# u2x.net
KiCad netlist of a schematic drawn in EAGLE
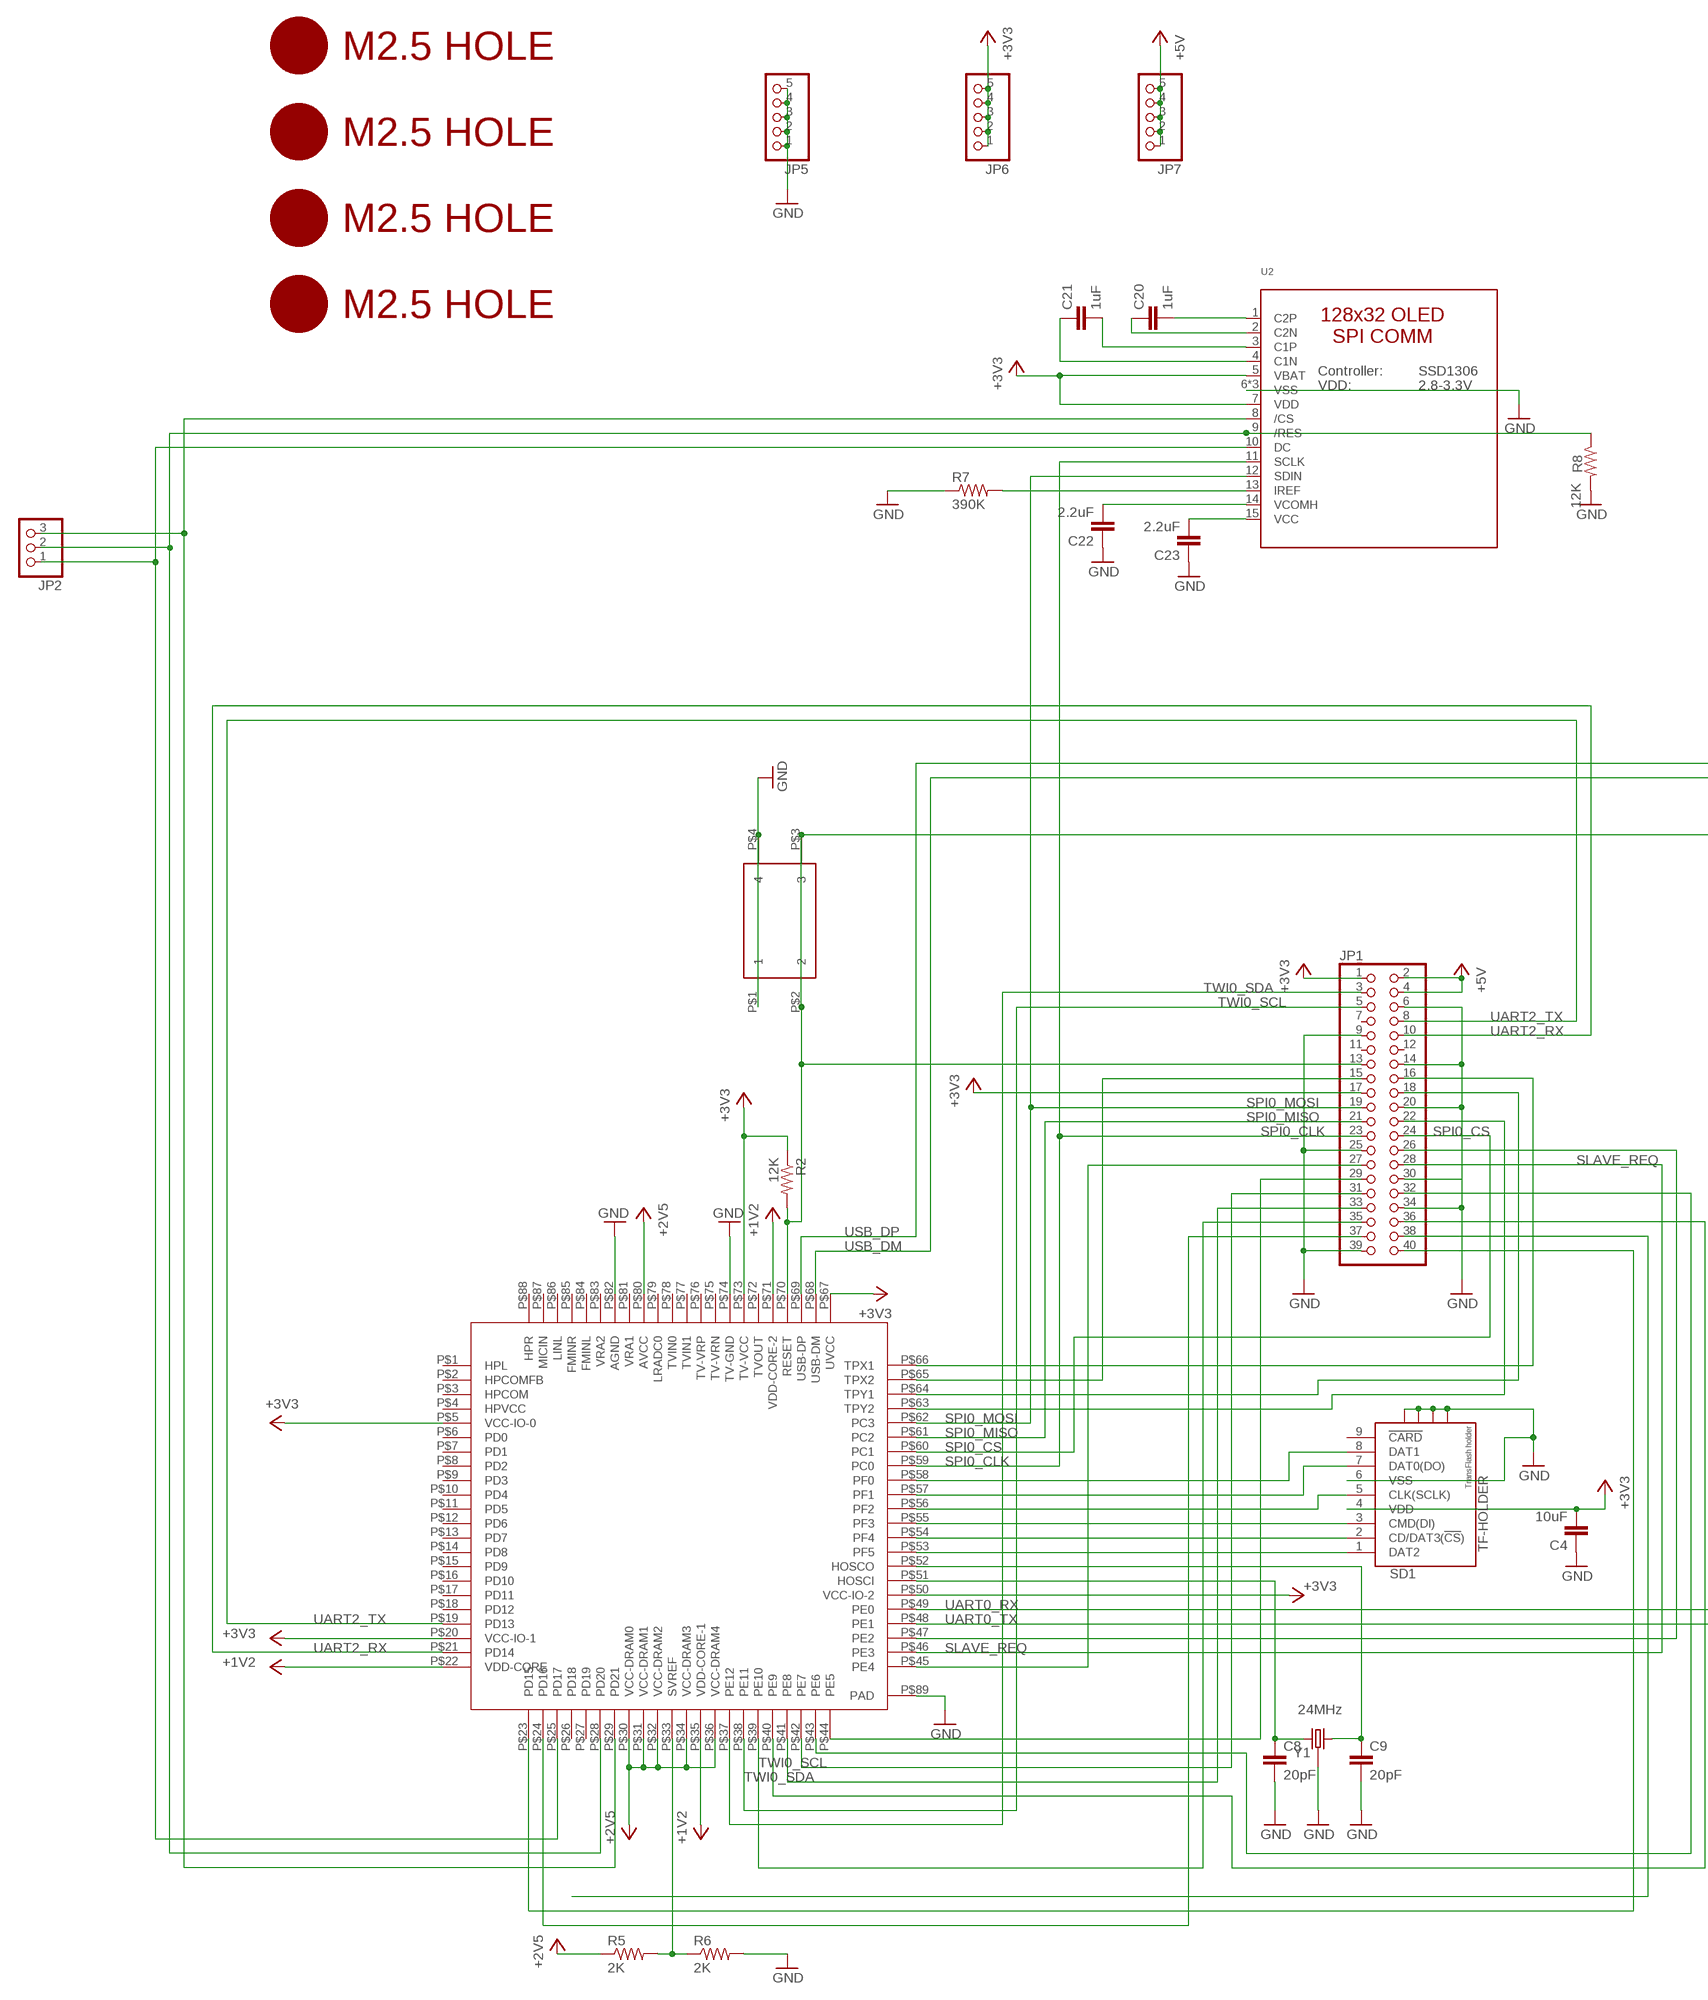
[diagram p0: schematic, sheet 1, part 1 of 2]
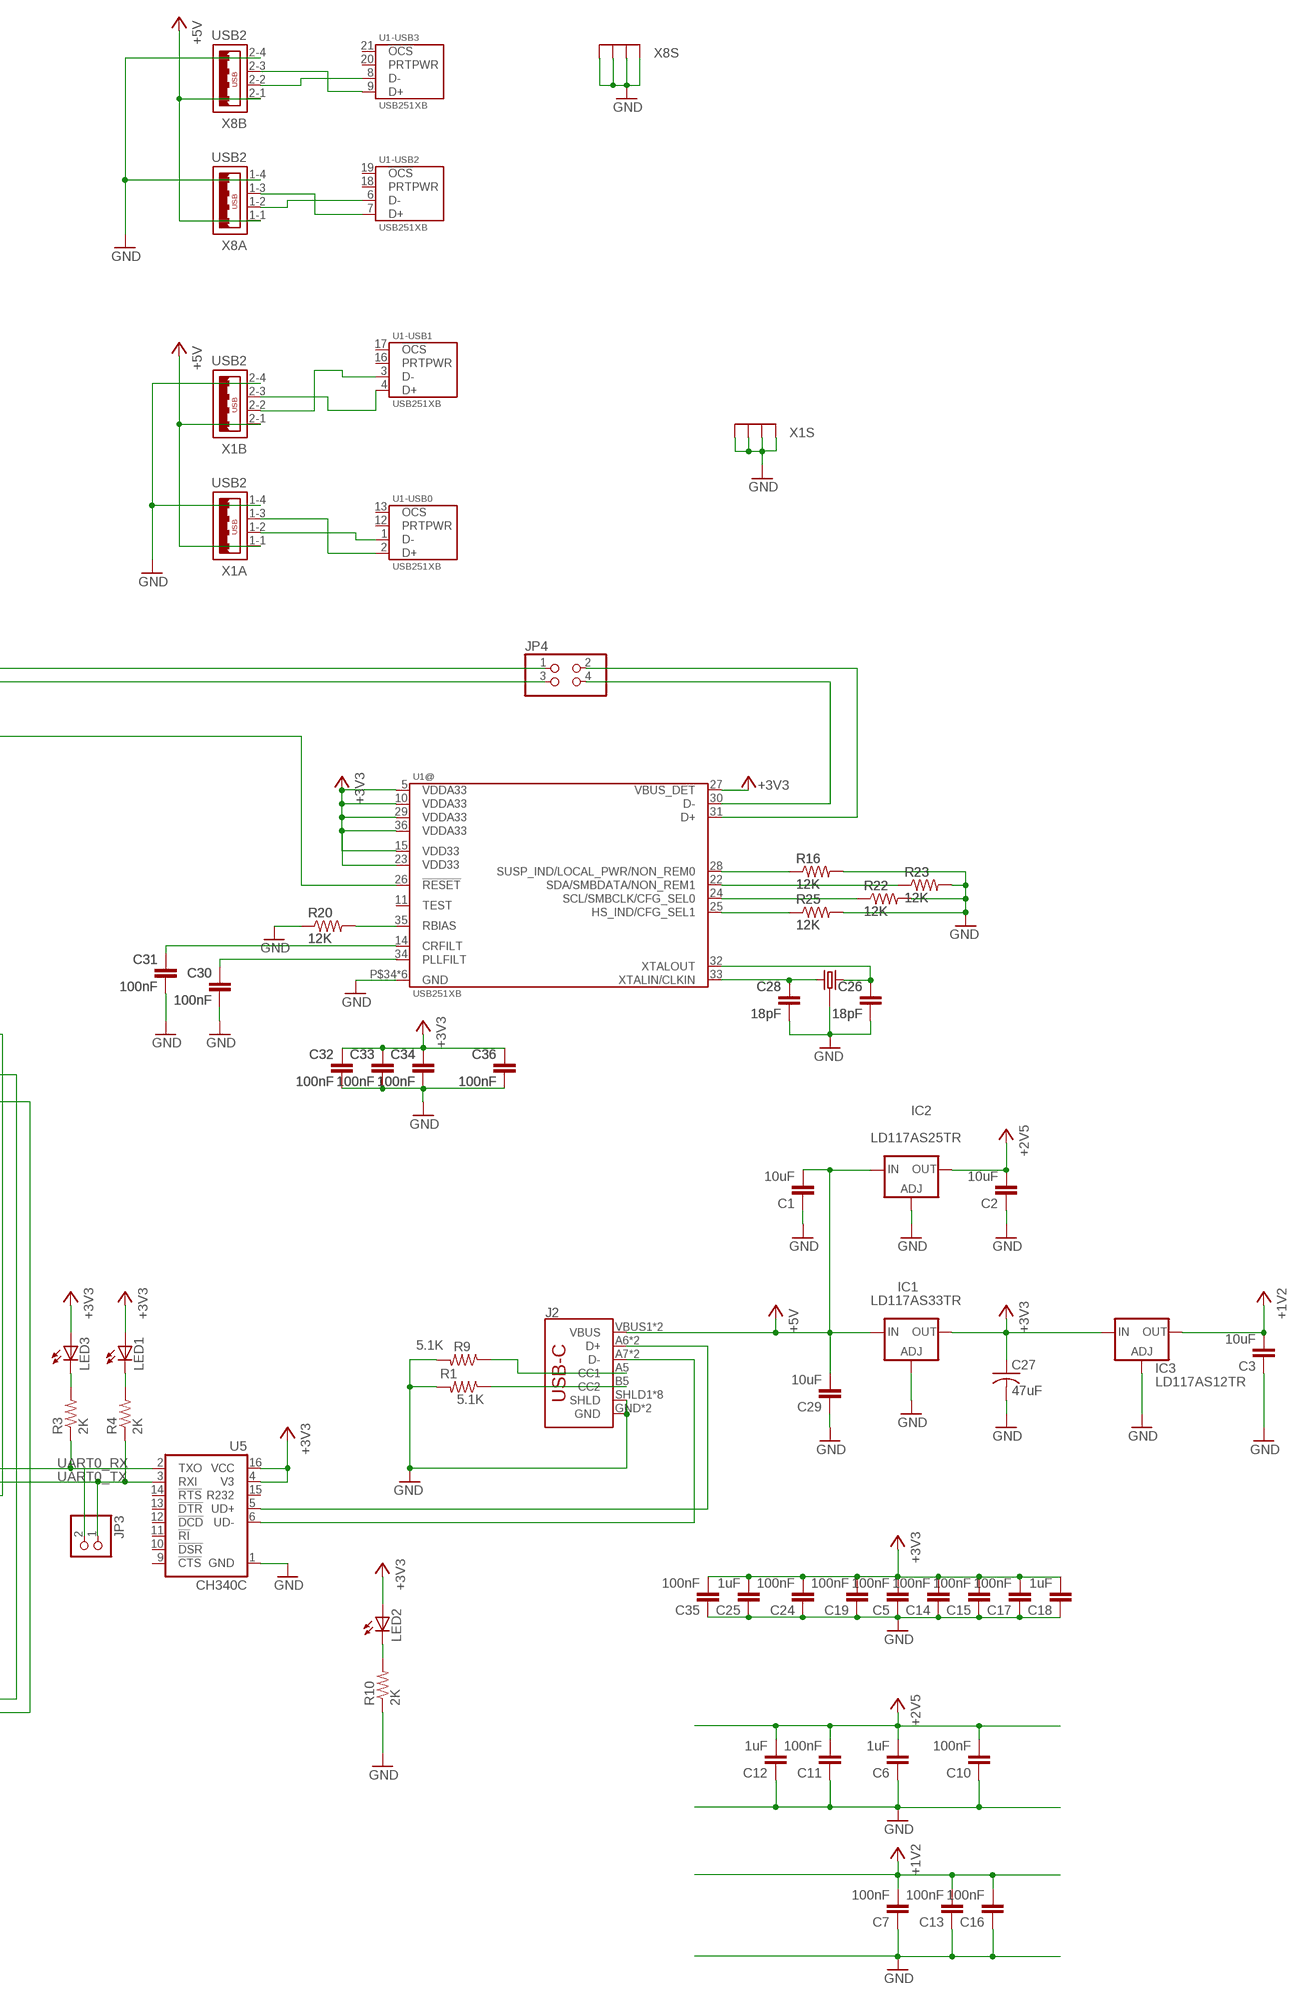
[diagram p1: schematic, sheet 1, part 2 of 2]

(export (version "E")
  (design (tool "Eeschema 10.0.6"))
  (components
    (comp (ref "C1")
      (value "10uF")
      (footprint "eagle-import:0805")
      (libsource (lib "eagle-import") (part "CAP0805"))
    )
    (comp (ref "C2")
      (value "10uF")
      (footprint "eagle-import:0805")
      (libsource (lib "eagle-import") (part "CAP0805"))
    )
    (comp (ref "C3")
      (value "10uF")
      (footprint "eagle-import:0805")
      (libsource (lib "eagle-import") (part "CAP0805"))
    )
    (comp (ref "C4")
      (value "10uF")
      (footprint "eagle-import:0805")
      (libsource (lib "eagle-import") (part "CAP0805"))
    )
    (comp (ref "C5")
      (value "100nF")
      (footprint "eagle-import:0805")
      (libsource (lib "eagle-import") (part "CAP0805"))
    )
    (comp (ref "C6")
      (value "1uF")
      (footprint "eagle-import:0805")
      (libsource (lib "eagle-import") (part "CAP0805"))
    )
    (comp (ref "C7")
      (value "100nF")
      (footprint "eagle-import:0805")
      (libsource (lib "eagle-import") (part "CAP0805"))
    )
    (comp (ref "C8")
      (value "20pF")
      (footprint "eagle-import:0805")
      (libsource (lib "eagle-import") (part "CAP0805"))
    )
    (comp (ref "C9")
      (value "20pF")
      (footprint "eagle-import:0805")
      (libsource (lib "eagle-import") (part "CAP0805"))
    )
    (comp (ref "C10")
      (value "100nF")
      (footprint "eagle-import:0805")
      (libsource (lib "eagle-import") (part "CAP0805"))
    )
    (comp (ref "C11")
      (value "100nF")
      (footprint "eagle-import:0805")
      (libsource (lib "eagle-import") (part "CAP0805"))
    )
    (comp (ref "C12")
      (value "1uF")
      (footprint "eagle-import:0805")
      (libsource (lib "eagle-import") (part "CAP0805"))
    )
    (comp (ref "C13")
      (value "100nF")
      (footprint "eagle-import:0805")
      (libsource (lib "eagle-import") (part "CAP0805"))
    )
    (comp (ref "C14")
      (value "100nF")
      (footprint "eagle-import:0805")
      (libsource (lib "eagle-import") (part "CAP0805"))
    )
    (comp (ref "C15")
      (value "100nF")
      (footprint "eagle-import:0805")
      (libsource (lib "eagle-import") (part "CAP0805"))
    )
    (comp (ref "C16")
      (value "100nF")
      (footprint "eagle-import:0805")
      (libsource (lib "eagle-import") (part "CAP0805"))
    )
    (comp (ref "C17")
      (value "100nF")
      (footprint "eagle-import:0805")
      (libsource (lib "eagle-import") (part "CAP0805"))
    )
    (comp (ref "C18")
      (value "1uF")
      (footprint "eagle-import:0805")
      (libsource (lib "eagle-import") (part "CAP0805"))
    )
    (comp (ref "C19")
      (value "100nF")
      (footprint "eagle-import:0805")
      (libsource (lib "eagle-import") (part "CAP0805"))
    )
    (comp (ref "C20")
      (value "1uF")
      (footprint "eagle-import:0805")
      (libsource (lib "eagle-import") (part "CAP0805"))
    )
    (comp (ref "C21")
      (value "1uF")
      (footprint "eagle-import:0805")
      (libsource (lib "eagle-import") (part "CAP0805"))
    )
    (comp (ref "C22")
      (value "2.2uF")
      (footprint "eagle-import:0805")
      (libsource (lib "eagle-import") (part "CAP0805"))
    )
    (comp (ref "C23")
      (value "2.2uF")
      (footprint "eagle-import:0805")
      (libsource (lib "eagle-import") (part "CAP0805"))
    )
    (comp (ref "C24")
      (value "100nF")
      (footprint "eagle-import:0805")
      (libsource (lib "eagle-import") (part "CAP0805"))
    )
    (comp (ref "C25")
      (value "1uF")
      (footprint "eagle-import:0805")
      (libsource (lib "eagle-import") (part "CAP0805"))
    )
    (comp (ref "C26")
      (value "18pF")
      (footprint "eagle-import:0805")
      (libsource (lib "eagle-import") (part "joyAnalog_CAP0805"))
    )
    (comp (ref "C27")
      (value "47uF")
      (footprint "eagle-import:C1210")
      (libsource (lib "eagle-import") (part "C-USC1210"))
    )
    (comp (ref "C28")
      (value "18pF")
      (footprint "eagle-import:0805")
      (libsource (lib "eagle-import") (part "joyAnalog_CAP0805"))
    )
    (comp (ref "C29")
      (value "10uF")
      (footprint "eagle-import:0805")
      (libsource (lib "eagle-import") (part "CAP0805"))
    )
    (comp (ref "C30")
      (value "100nF")
      (footprint "eagle-import:0805")
      (libsource (lib "eagle-import") (part "joyAnalog_CAP0805"))
    )
    (comp (ref "C31")
      (value "100nF")
      (footprint "eagle-import:0805")
      (libsource (lib "eagle-import") (part "joyAnalog_CAP0805"))
    )
    (comp (ref "C32")
      (value "100nF")
      (footprint "eagle-import:0805")
      (libsource (lib "eagle-import") (part "joyAnalog_CAP0805"))
    )
    (comp (ref "C33")
      (value "100nF")
      (footprint "eagle-import:0805")
      (libsource (lib "eagle-import") (part "joyAnalog_CAP0805"))
    )
    (comp (ref "C34")
      (value "100nF")
      (footprint "eagle-import:0805")
      (libsource (lib "eagle-import") (part "joyAnalog_CAP0805"))
    )
    (comp (ref "C35")
      (value "100nF")
      (footprint "eagle-import:0805")
      (libsource (lib "eagle-import") (part "CAP0805"))
    )
    (comp (ref "C36")
      (value "100nF")
      (footprint "eagle-import:0805")
      (libsource (lib "eagle-import") (part "joyAnalog_CAP0805"))
    )
    (comp (ref "IC1")
      (value "LD117AS33TR")
      (footprint "eagle-import:SOT223")
      (libsource (lib "eagle-import") (part "LD117A?S33TR"))
    )
    (comp (ref "IC2")
      (value "LD117AS25TR")
      (footprint "eagle-import:SOT223")
      (libsource (lib "eagle-import") (part "LD117A?S25TR"))
    )
    (comp (ref "IC3")
      (value "LD117AS12TR")
      (footprint "eagle-import:SOT223")
      (libsource (lib "eagle-import") (part "LD117A?S12TR"))
    )
    (comp (ref "J2")
      (value "USB_C16PIN")
      (footprint "eagle-import:USB-C-16P")
      (libsource (lib "eagle-import") (part "USB_C16PIN"))
    )
    (comp (ref "JP1")
      (value "PINHD-2X20-BIG")
      (footprint "eagle-import:2X20-BIG")
      (libsource (lib "eagle-import") (part "PINHD-2X20-BIG"))
    )
    (comp (ref "JP2")
      (value "PINHD-1X3CB")
      (footprint "eagle-import:1X03-CLEANBIG")
      (libsource (lib "eagle-import") (part "PINHD-1X3CB"))
    )
    (comp (ref "JP3")
      (value "PINHD-1X2")
      (footprint "eagle-import:1X02")
      (libsource (lib "eagle-import") (part "PINHD-1X2"))
    )
    (comp (ref "JP4")
      (value "PINHD-2X2")
      (footprint "eagle-import:2X02")
      (libsource (lib "eagle-import") (part "PINHD-2X2"))
    )
    (comp (ref "JP5")
      (value "PINHD-1X5")
      (footprint "eagle-import:1X05")
      (libsource (lib "eagle-import") (part "PINHD-1X5"))
    )
    (comp (ref "JP6")
      (value "PINHD-1X5")
      (footprint "eagle-import:1X05")
      (libsource (lib "eagle-import") (part "PINHD-1X5"))
    )
    (comp (ref "JP7")
      (value "PINHD-1X5")
      (footprint "eagle-import:1X05")
      (libsource (lib "eagle-import") (part "PINHD-1X5"))
    )
    (comp (ref "LED1")
      (value "LEDCHIP-LED0805")
      (footprint "eagle-import:CHIP-LED0805")
      (libsource (lib "eagle-import") (part "LEDCHIP-LED0805"))
    )
    (comp (ref "LED2")
      (value "LEDCHIP-LED0805")
      (footprint "eagle-import:CHIP-LED0805")
      (libsource (lib "eagle-import") (part "LEDCHIP-LED0805"))
    )
    (comp (ref "LED3")
      (value "LEDCHIP-LED0805")
      (footprint "eagle-import:CHIP-LED0805")
      (libsource (lib "eagle-import") (part "LEDCHIP-LED0805"))
    )
    (comp (ref "R1")
      (value "5.1K")
      (footprint "eagle-import:0805")
      (libsource (lib "eagle-import") (part "joyAnalog_RESISTOR0805-RES"))
    )
    (comp (ref "R2")
      (value "12K")
      (footprint "eagle-import:0805")
      (libsource (lib "eagle-import") (part "RESISTOR0805-RES"))
    )
    (comp (ref "R3")
      (value "2K")
      (footprint "eagle-import:0805")
      (libsource (lib "eagle-import") (part "RESISTOR0805-RES"))
    )
    (comp (ref "R4")
      (value "2K")
      (footprint "eagle-import:0805")
      (libsource (lib "eagle-import") (part "RESISTOR0805-RES"))
    )
    (comp (ref "R5")
      (value "2K")
      (footprint "eagle-import:0805")
      (libsource (lib "eagle-import") (part "RESISTOR0805-RES"))
    )
    (comp (ref "R6")
      (value "2K")
      (footprint "eagle-import:0805")
      (libsource (lib "eagle-import") (part "RESISTOR0805-RES"))
    )
    (comp (ref "R7")
      (value "390K")
      (footprint "eagle-import:0805")
      (libsource (lib "eagle-import") (part "RESISTOR0805-RES"))
    )
    (comp (ref "R8")
      (value "12K")
      (footprint "eagle-import:0805")
      (libsource (lib "eagle-import") (part "joyAnalog_RESISTOR0805-RES"))
    )
    (comp (ref "R9")
      (value "5.1K")
      (footprint "eagle-import:0805")
      (libsource (lib "eagle-import") (part "joyAnalog_RESISTOR0805-RES"))
    )
    (comp (ref "R10")
      (value "2K")
      (footprint "eagle-import:0805")
      (libsource (lib "eagle-import") (part "RESISTOR0805-RES"))
    )
    (comp (ref "R16")
      (value "12K")
      (footprint "eagle-import:0805")
      (libsource (lib "eagle-import") (part "joyAnalog_RESISTOR0805-RES"))
    )
    (comp (ref "R20")
      (value "12K")
      (footprint "eagle-import:0805")
      (libsource (lib "eagle-import") (part "joyAnalog_RESISTOR0805-RES"))
    )
    (comp (ref "R22")
      (value "12K")
      (footprint "eagle-import:0805")
      (libsource (lib "eagle-import") (part "joyAnalog_RESISTOR0805-RES"))
    )
    (comp (ref "R23")
      (value "12K")
      (footprint "eagle-import:0805")
      (libsource (lib "eagle-import") (part "joyAnalog_RESISTOR0805-RES"))
    )
    (comp (ref "R25")
      (value "12K")
      (footprint "eagle-import:0805")
      (libsource (lib "eagle-import") (part "joyAnalog_RESISTOR0805-RES"))
    )
    (comp (ref "SD1")
      (value "TF-HOLDER")
      (footprint "eagle-import:TF-PULL")
      (libsource (lib "eagle-import") (part "TF-HOLDER"))
    )
    (comp (ref "SW20")
      (value "324_SW")
      (footprint "eagle-import:342_SWICH_FOOT")
      (libsource (lib "eagle-import") (part "324_SW"))
    )
    (comp (ref "U$1")
      (value "F1C100S_DEV")
      (footprint "eagle-import:MQFN88")
      (libsource (lib "eagle-import") (part "F1C100S_DEV"))
    )
    (comp (ref "U$2")
      (value "M2.5HOLE")
      (footprint "eagle-import:M2.5HOLE")
      (libsource (lib "eagle-import") (part "M2.5HOLE"))
    )
    (comp (ref "U$3")
      (value "M2.5HOLE")
      (footprint "eagle-import:M2.5HOLE")
      (libsource (lib "eagle-import") (part "M2.5HOLE"))
    )
    (comp (ref "U$4")
      (value "M2.5HOLE")
      (footprint "eagle-import:M2.5HOLE")
      (libsource (lib "eagle-import") (part "M2.5HOLE"))
    )
    (comp (ref "U$5")
      (value "M2.5HOLE")
      (footprint "eagle-import:M2.5HOLE")
      (libsource (lib "eagle-import") (part "M2.5HOLE"))
    )
    (comp (ref "U$16")
      (value "CRYSTAL-GROUNDED")
      (footprint "eagle-import:CRYSTAL-SMD-5X3")
      (libsource (lib "eagle-import") (part "CRYSTAL-GROUNDED"))
    )
    (comp (ref "U1")
      (value "USB251XB")
      (footprint "eagle-import:QFN-36")
      (libsource (lib "eagle-import") (part "USB251XB"))
    )
    (comp (ref "U2")
      (value "LUL_DISP_OLED_UG-2864HSWEG01")
      (footprint "eagle-import:LUL_UG-2864HSWEG01_1.3_WRAPAROUND")
      (libsource (lib "eagle-import") (part "LUL_DISP_OLED_UG-2864HSWEG01"))
    )
    (comp (ref "U5")
      (value "CH340C")
      (footprint "eagle-import:SO016")
      (libsource (lib "eagle-import") (part "CH340C"))
    )
    (comp (ref "X1")
      (value "USB2")
      (footprint "eagle-import:USB2")
      (libsource (lib "eagle-import") (part "USB2"))
    )
    (comp (ref "X8")
      (value "USB2")
      (footprint "eagle-import:USB2")
      (libsource (lib "eagle-import") (part "USB2"))
    )
    (comp (ref "Y1")
      (value "24MHz")
      (footprint "eagle-import:CRYSTAL-SMD-3.2X2.5MM")
      (libsource (lib "eagle-import") (part "CRYSTAL-26MHZSMD-3.2X2.5"))
    )
  )
  (nets
    (net (code "1") (name "+1V2") (class "Default")
      (node (ref "C13") (pin "2") (pinfunction "2_2") (pintype "passive"))
      (node (ref "C16") (pin "2") (pinfunction "2_2") (pintype "passive"))
      (node (ref "C3") (pin "2") (pinfunction "2_2") (pintype "passive"))
      (node (ref "C7") (pin "2") (pinfunction "2_2") (pintype "passive"))
      (node (ref "IC3") (pin "4") (pinfunction "OUT_4") (pintype "passive"))
      (node (ref "U$1") (pin "P$22") (pinfunction "VDD-CORE_P$22") (pintype "bidirectional"))
      (node (ref "U$1") (pin "P$35") (pinfunction "VDD-CORE-1_P$35") (pintype "bidirectional"))
      (node (ref "U$1") (pin "P$71") (pinfunction "VDD-CORE-2_P$71") (pintype "bidirectional"))
    )
    (net (code "2") (name "+2V5") (class "Default")
      (node (ref "C10") (pin "2") (pinfunction "2_2") (pintype "passive"))
      (node (ref "C11") (pin "2") (pinfunction "2_2") (pintype "passive"))
      (node (ref "C12") (pin "2") (pinfunction "2_2") (pintype "passive"))
      (node (ref "C2") (pin "2") (pinfunction "2_2") (pintype "passive"))
      (node (ref "C6") (pin "2") (pinfunction "2_2") (pintype "passive"))
      (node (ref "IC2") (pin "4") (pinfunction "OUT_4") (pintype "passive"))
      (node (ref "R5") (pin "1") (pinfunction "1_1") (pintype "passive"))
      (node (ref "U$1") (pin "P$30") (pinfunction "VCC-DRAM0_P$30") (pintype "bidirectional"))
      (node (ref "U$1") (pin "P$31") (pinfunction "VCC-DRAM1_P$31") (pintype "bidirectional"))
      (node (ref "U$1") (pin "P$32") (pinfunction "VCC-DRAM2_P$32") (pintype "bidirectional"))
      (node (ref "U$1") (pin "P$34") (pinfunction "VCC-DRAM3_P$34") (pintype "bidirectional"))
      (node (ref "U$1") (pin "P$36") (pinfunction "VCC-DRAM4_P$36") (pintype "bidirectional"))
      (node (ref "U$1") (pin "P$80") (pinfunction "AVCC_P$80") (pintype "bidirectional"))
    )
    (net (code "3") (name "+3V3") (class "Default")
      (node (ref "C14") (pin "2") (pinfunction "2_2") (pintype "passive"))
      (node (ref "C15") (pin "2") (pinfunction "2_2") (pintype "passive"))
      (node (ref "C17") (pin "2") (pinfunction "2_2") (pintype "passive"))
      (node (ref "C18") (pin "2") (pinfunction "2_2") (pintype "passive"))
      (node (ref "C19") (pin "2") (pinfunction "2_2") (pintype "passive"))
      (node (ref "C24") (pin "2") (pinfunction "2_2") (pintype "passive"))
      (node (ref "C25") (pin "2") (pinfunction "2_2") (pintype "passive"))
      (node (ref "C27") (pin "1") (pinfunction "1_1") (pintype "passive"))
      (node (ref "C32") (pin "1") (pinfunction "1_1") (pintype "passive"))
      (node (ref "C33") (pin "1") (pinfunction "1_1") (pintype "passive"))
      (node (ref "C34") (pin "1") (pinfunction "1_1") (pintype "passive"))
      (node (ref "C35") (pin "2") (pinfunction "2_2") (pintype "passive"))
      (node (ref "C36") (pin "1") (pinfunction "1_1") (pintype "passive"))
      (node (ref "C4") (pin "2") (pinfunction "2_2") (pintype "passive"))
      (node (ref "C5") (pin "2") (pinfunction "2_2") (pintype "passive"))
      (node (ref "IC1") (pin "4") (pinfunction "OUT_4") (pintype "passive"))
      (node (ref "IC3") (pin "3") (pinfunction "IN_3") (pintype "input"))
      (node (ref "JP1") (pin "1") (pinfunction "1_1") (pintype "passive"))
      (node (ref "JP1") (pin "17") (pinfunction "17_17") (pintype "passive"))
      (node (ref "JP6") (pin "1") (pinfunction "1_1") (pintype "passive"))
      (node (ref "JP6") (pin "2") (pinfunction "2_2") (pintype "passive"))
      (node (ref "JP6") (pin "3") (pinfunction "3_3") (pintype "passive"))
      (node (ref "JP6") (pin "4") (pinfunction "4_4") (pintype "passive"))
      (node (ref "JP6") (pin "5") (pinfunction "5_5") (pintype "passive"))
      (node (ref "LED1") (pin "A") (pinfunction "A_A") (pintype "passive"))
      (node (ref "LED2") (pin "A") (pinfunction "A_A") (pintype "passive"))
      (node (ref "LED3") (pin "A") (pinfunction "A_A") (pintype "passive"))
      (node (ref "R2") (pin "1") (pinfunction "1_1") (pintype "passive"))
      (node (ref "SD1") (pin "4") (pinfunction "VDD_4") (pintype "power_in"))
      (node (ref "U$1") (pin "P$20") (pinfunction "VCC-IO-1_P$20") (pintype "bidirectional"))
      (node (ref "U$1") (pin "P$5") (pinfunction "VCC-IO-0_P$5") (pintype "bidirectional"))
      (node (ref "U$1") (pin "P$50") (pinfunction "VCC-IO-2_P$50") (pintype "bidirectional"))
      (node (ref "U$1") (pin "P$67") (pinfunction "UVCC_P$67") (pintype "bidirectional"))
      (node (ref "U$1") (pin "P$73") (pinfunction "TV-VCC_P$73") (pintype "bidirectional"))
      (node (ref "U1") (pin "10") (pinfunction "VDDA33_10") (pintype "bidirectional"))
      (node (ref "U1") (pin "15") (pinfunction "VDD33_15") (pintype "bidirectional"))
      (node (ref "U1") (pin "23") (pinfunction "VDD33_23") (pintype "bidirectional"))
      (node (ref "U1") (pin "27") (pinfunction "VBUS_DET_27") (pintype "bidirectional"))
      (node (ref "U1") (pin "29") (pinfunction "VDDA33_29") (pintype "bidirectional"))
      (node (ref "U1") (pin "36") (pinfunction "VDDA33_36") (pintype "bidirectional"))
      (node (ref "U1") (pin "5") (pinfunction "VDDA33_5") (pintype "bidirectional"))
      (node (ref "U2") (pin "5") (pinfunction "VBAT_5") (pintype "input"))
      (node (ref "U2") (pin "7") (pinfunction "VDD_7") (pintype "power_in"))
      (node (ref "U5") (pin "16") (pinfunction "VCC_16") (pintype "bidirectional"))
      (node (ref "U5") (pin "4") (pinfunction "V3_4") (pintype "bidirectional"))
    )
    (net (code "4") (name "+5V") (class "Default")
      (node (ref "C1") (pin "2") (pinfunction "2_2") (pintype "passive"))
      (node (ref "C29") (pin "2") (pinfunction "2_2") (pintype "passive"))
      (node (ref "IC1") (pin "3") (pinfunction "IN_3") (pintype "input"))
      (node (ref "IC2") (pin "3") (pinfunction "IN_3") (pintype "input"))
      (node (ref "J2") (pin "VBUS1") (pinfunction "VBUS_VBUS1") (pintype "bidirectional"))
      (node (ref "J2") (pin "VBUS2") (pinfunction "VBUS_VBUS2") (pintype "bidirectional"))
      (node (ref "JP1") (pin "2") (pinfunction "2_2") (pintype "passive"))
      (node (ref "JP1") (pin "4") (pinfunction "4_4") (pintype "passive"))
      (node (ref "JP7") (pin "1") (pinfunction "1_1") (pintype "passive"))
      (node (ref "JP7") (pin "2") (pinfunction "2_2") (pintype "passive"))
      (node (ref "JP7") (pin "3") (pinfunction "3_3") (pintype "passive"))
      (node (ref "JP7") (pin "4") (pinfunction "4_4") (pintype "passive"))
      (node (ref "JP7") (pin "5") (pinfunction "5_5") (pintype "passive"))
      (node (ref "X1") (pin "1-1") (pinfunction "1_1-1") (pintype "passive"))
      (node (ref "X1") (pin "2-1") (pinfunction "1_2-1") (pintype "passive"))
      (node (ref "X8") (pin "1-1") (pinfunction "1_1-1") (pintype "passive"))
      (node (ref "X8") (pin "2-1") (pinfunction "1_2-1") (pintype "passive"))
    )
    (net (code "5") (name "/SLAVE_REQ") (class "Default")
      (node (ref "JP1") (pin "28") (pinfunction "28_28") (pintype "passive"))
      (node (ref "U$1") (pin "P$46") (pinfunction "PE3_P$46") (pintype "bidirectional"))
    )
    (net (code "6") (name "/SPI0_CLK") (class "Default")
      (node (ref "JP1") (pin "23") (pinfunction "23_23") (pintype "passive"))
      (node (ref "U$1") (pin "P$59") (pinfunction "PC0_P$59") (pintype "bidirectional"))
      (node (ref "U2") (pin "11") (pinfunction "SCLK_11") (pintype "bidirectional"))
    )
    (net (code "7") (name "/SPI0_CS") (class "Default")
      (node (ref "JP1") (pin "24") (pinfunction "24_24") (pintype "passive"))
      (node (ref "U$1") (pin "P$60") (pinfunction "PC1_P$60") (pintype "bidirectional"))
    )
    (net (code "8") (name "/SPI0_MISO") (class "Default")
      (node (ref "JP1") (pin "21") (pinfunction "21_21") (pintype "passive"))
      (node (ref "U$1") (pin "P$61") (pinfunction "PC2_P$61") (pintype "bidirectional"))
    )
    (net (code "9") (name "/SPI0_MOSI") (class "Default")
      (node (ref "JP1") (pin "19") (pinfunction "19_19") (pintype "passive"))
      (node (ref "U$1") (pin "P$62") (pinfunction "PC3_P$62") (pintype "bidirectional"))
      (node (ref "U2") (pin "12") (pinfunction "SDIN_12") (pintype "bidirectional"))
    )
    (net (code "10") (name "/TWI0_SCL") (class "Default")
      (node (ref "JP1") (pin "5") (pinfunction "5_5") (pintype "passive"))
      (node (ref "U$1") (pin "P$38") (pinfunction "PE11_P$38") (pintype "bidirectional"))
    )
    (net (code "11") (name "/TWI0_SDA") (class "Default")
      (node (ref "JP1") (pin "3") (pinfunction "3_3") (pintype "passive"))
      (node (ref "U$1") (pin "P$37") (pinfunction "PE12_P$37") (pintype "bidirectional"))
    )
    (net (code "12") (name "/UART0_RX") (class "Default")
      (node (ref "JP3") (pin "2") (pinfunction "2_2") (pintype "passive"))
      (node (ref "R3") (pin "1") (pinfunction "1_1") (pintype "passive"))
      (node (ref "U$1") (pin "P$49") (pinfunction "PE0_P$49") (pintype "bidirectional"))
      (node (ref "U5") (pin "2") (pinfunction "TXO_2") (pintype "bidirectional"))
    )
    (net (code "13") (name "/UART0_TX") (class "Default")
      (node (ref "JP3") (pin "1") (pinfunction "1_1") (pintype "passive"))
      (node (ref "R4") (pin "1") (pinfunction "1_1") (pintype "passive"))
      (node (ref "U$1") (pin "P$48") (pinfunction "PE1_P$48") (pintype "bidirectional"))
      (node (ref "U5") (pin "3") (pinfunction "RXI_3") (pintype "bidirectional"))
    )
    (net (code "14") (name "/UART2_RX") (class "Default")
      (node (ref "JP1") (pin "10") (pinfunction "10_10") (pintype "passive"))
      (node (ref "U$1") (pin "P$21") (pinfunction "PD14_P$21") (pintype "bidirectional"))
    )
    (net (code "15") (name "/UART2_TX") (class "Default")
      (node (ref "JP1") (pin "8") (pinfunction "8_8") (pintype "passive"))
      (node (ref "U$1") (pin "P$19") (pinfunction "PD13_P$19") (pintype "bidirectional"))
    )
    (net (code "16") (name "/USB_DM") (class "Default")
      (node (ref "JP4") (pin "3") (pinfunction "3_3") (pintype "passive"))
      (node (ref "U$1") (pin "P$68") (pinfunction "USB-DM_P$68") (pintype "bidirectional"))
    )
    (net (code "17") (name "/USB_DP") (class "Default")
      (node (ref "JP4") (pin "1") (pinfunction "1_1") (pintype "passive"))
      (node (ref "U$1") (pin "P$69") (pinfunction "USB-DP_P$69") (pintype "bidirectional"))
    )
    (net (code "18") (name "GND") (class "Default")
      (node (ref "C1") (pin "1") (pinfunction "1_1") (pintype "passive"))
      (node (ref "C10") (pin "1") (pinfunction "1_1") (pintype "passive"))
      (node (ref "C11") (pin "1") (pinfunction "1_1") (pintype "passive"))
      (node (ref "C12") (pin "1") (pinfunction "1_1") (pintype "passive"))
      (node (ref "C13") (pin "1") (pinfunction "1_1") (pintype "passive"))
      (node (ref "C14") (pin "1") (pinfunction "1_1") (pintype "passive"))
      (node (ref "C15") (pin "1") (pinfunction "1_1") (pintype "passive"))
      (node (ref "C16") (pin "1") (pinfunction "1_1") (pintype "passive"))
      (node (ref "C17") (pin "1") (pinfunction "1_1") (pintype "passive"))
      (node (ref "C18") (pin "1") (pinfunction "1_1") (pintype "passive"))
      (node (ref "C19") (pin "1") (pinfunction "1_1") (pintype "passive"))
      (node (ref "C2") (pin "1") (pinfunction "1_1") (pintype "passive"))
      (node (ref "C22") (pin "1") (pinfunction "1_1") (pintype "passive"))
      (node (ref "C23") (pin "1") (pinfunction "1_1") (pintype "passive"))
      (node (ref "C24") (pin "1") (pinfunction "1_1") (pintype "passive"))
      (node (ref "C25") (pin "1") (pinfunction "1_1") (pintype "passive"))
      (node (ref "C26") (pin "2") (pinfunction "2_2") (pintype "passive"))
      (node (ref "C27") (pin "2") (pinfunction "2_2") (pintype "passive"))
      (node (ref "C28") (pin "2") (pinfunction "2_2") (pintype "passive"))
      (node (ref "C29") (pin "1") (pinfunction "1_1") (pintype "passive"))
      (node (ref "C3") (pin "1") (pinfunction "1_1") (pintype "passive"))
      (node (ref "C30") (pin "2") (pinfunction "2_2") (pintype "passive"))
      (node (ref "C31") (pin "2") (pinfunction "2_2") (pintype "passive"))
      (node (ref "C32") (pin "2") (pinfunction "2_2") (pintype "passive"))
      (node (ref "C33") (pin "2") (pinfunction "2_2") (pintype "passive"))
      (node (ref "C34") (pin "2") (pinfunction "2_2") (pintype "passive"))
      (node (ref "C35") (pin "1") (pinfunction "1_1") (pintype "passive"))
      (node (ref "C36") (pin "2") (pinfunction "2_2") (pintype "passive"))
      (node (ref "C4") (pin "1") (pinfunction "1_1") (pintype "passive"))
      (node (ref "C5") (pin "1") (pinfunction "1_1") (pintype "passive"))
      (node (ref "C6") (pin "1") (pinfunction "1_1") (pintype "passive"))
      (node (ref "C7") (pin "1") (pinfunction "1_1") (pintype "passive"))
      (node (ref "C8") (pin "2") (pinfunction "2_2") (pintype "passive"))
      (node (ref "C9") (pin "2") (pinfunction "2_2") (pintype "passive"))
      (node (ref "IC1") (pin "1") (pinfunction "ADJ_1") (pintype "input"))
      (node (ref "IC2") (pin "1") (pinfunction "ADJ_1") (pintype "input"))
      (node (ref "IC3") (pin "1") (pinfunction "ADJ_1") (pintype "input"))
      (node (ref "J2") (pin "GND") (pinfunction "GND_GND") (pintype "bidirectional"))
      (node (ref "J2") (pin "GND2") (pinfunction "GND_GND2") (pintype "bidirectional"))
      (node (ref "J2") (pin "SHLD1") (pinfunction "SHLD_SHLD1") (pintype "bidirectional"))
      (node (ref "J2") (pin "SHLD2") (pinfunction "SHLD_SHLD2") (pintype "bidirectional"))
      (node (ref "J2") (pin "SHLD3") (pinfunction "SHLD_SHLD3") (pintype "bidirectional"))
      (node (ref "J2") (pin "SHLD4") (pinfunction "SHLD_SHLD4") (pintype "bidirectional"))
      (node (ref "J2") (pin "SHLD5") (pinfunction "SHLD_SHLD5") (pintype "bidirectional"))
      (node (ref "J2") (pin "SHLD6") (pinfunction "SHLD_SHLD6") (pintype "bidirectional"))
      (node (ref "J2") (pin "SHLD7") (pinfunction "SHLD_SHLD7") (pintype "bidirectional"))
      (node (ref "J2") (pin "SHLD8") (pinfunction "SHLD_SHLD8") (pintype "bidirectional"))
      (node (ref "JP1") (pin "14") (pinfunction "14_14") (pintype "passive"))
      (node (ref "JP1") (pin "20") (pinfunction "20_20") (pintype "passive"))
      (node (ref "JP1") (pin "25") (pinfunction "25_25") (pintype "passive"))
      (node (ref "JP1") (pin "30") (pinfunction "30_30") (pintype "passive"))
      (node (ref "JP1") (pin "34") (pinfunction "34_34") (pintype "passive"))
      (node (ref "JP1") (pin "39") (pinfunction "39_39") (pintype "passive"))
      (node (ref "JP1") (pin "6") (pinfunction "6_6") (pintype "passive"))
      (node (ref "JP1") (pin "9") (pinfunction "9_9") (pintype "passive"))
      (node (ref "JP5") (pin "1") (pinfunction "1_1") (pintype "passive"))
      (node (ref "JP5") (pin "2") (pinfunction "2_2") (pintype "passive"))
      (node (ref "JP5") (pin "3") (pinfunction "3_3") (pintype "passive"))
      (node (ref "JP5") (pin "4") (pinfunction "4_4") (pintype "passive"))
      (node (ref "JP5") (pin "5") (pinfunction "5_5") (pintype "passive"))
      (node (ref "R1") (pin "2") (pinfunction "2_2") (pintype "passive"))
      (node (ref "R10") (pin "1") (pinfunction "1_1") (pintype "passive"))
      (node (ref "R16") (pin "2") (pinfunction "2_2") (pintype "passive"))
      (node (ref "R20") (pin "1") (pinfunction "1_1") (pintype "passive"))
      (node (ref "R22") (pin "2") (pinfunction "2_2") (pintype "passive"))
      (node (ref "R23") (pin "2") (pinfunction "2_2") (pintype "passive"))
      (node (ref "R25") (pin "2") (pinfunction "2_2") (pintype "passive"))
      (node (ref "R6") (pin "2") (pinfunction "2_2") (pintype "passive"))
      (node (ref "R7") (pin "1") (pinfunction "1_1") (pintype "passive"))
      (node (ref "R8") (pin "2") (pinfunction "2_2") (pintype "passive"))
      (node (ref "R9") (pin "2") (pinfunction "2_2") (pintype "passive"))
      (node (ref "SD1") (pin "6") (pinfunction "VSS_6") (pintype "power_in"))
      (node (ref "SD1") (pin "S1") (pinfunction "S1_S1") (pintype "passive"))
      (node (ref "SD1") (pin "S2") (pinfunction "S2_S2") (pintype "passive"))
      (node (ref "SD1") (pin "S3") (pinfunction "S3_S3") (pintype "passive"))
      (node (ref "SD1") (pin "S4") (pinfunction "S4_S4") (pintype "passive"))
      (node (ref "SW20") (pin "P$1") (pinfunction "1_P$1") (pintype "bidirectional"))
      (node (ref "SW20") (pin "P$4") (pinfunction "4_P$4") (pintype "bidirectional"))
      (node (ref "U$1") (pin "P$74") (pinfunction "TV-GND_P$74") (pintype "bidirectional"))
      (node (ref "U$1") (pin "P$82") (pinfunction "AGND_P$82") (pintype "bidirectional"))
      (node (ref "U$1") (pin "P$89") (pinfunction "PAD_P$89") (pintype "bidirectional"))
      (node (ref "U$16") (pin "2") (pinfunction "3_2") (pintype "passive"))
      (node (ref "U$16") (pin "4") (pinfunction "3_4") (pintype "passive"))
      (node (ref "U1") (pin "P$34") (pinfunction "GND_P$34") (pintype "bidirectional"))
      (node (ref "U1") (pin "P$35") (pinfunction "GND_P$35") (pintype "bidirectional"))
      (node (ref "U1") (pin "P$36") (pinfunction "GND_P$36") (pintype "bidirectional"))
      (node (ref "U1") (pin "P$37") (pinfunction "GND_P$37") (pintype "bidirectional"))
      (node (ref "U1") (pin "P$38") (pinfunction "GND_P$38") (pintype "bidirectional"))
      (node (ref "U1") (pin "PAD") (pinfunction "GND_PAD") (pintype "bidirectional"))
      (node (ref "U2") (pin "16") (pinfunction "VSS_16") (pintype "power_in"))
      (node (ref "U2") (pin "17") (pinfunction "VSS_17") (pintype "power_in"))
      (node (ref "U2") (pin "6") (pinfunction "VSS_6") (pintype "power_in"))
      (node (ref "U5") (pin "1") (pinfunction "GND_1") (pintype "bidirectional"))
      (node (ref "X1") (pin "1-4") (pinfunction "4_1-4") (pintype "passive"))
      (node (ref "X1") (pin "2-4") (pinfunction "4_2-4") (pintype "passive"))
      (node (ref "X1") (pin "M1") (pinfunction "S1_M1") (pintype "passive"))
      (node (ref "X1") (pin "M2") (pinfunction "S2_M2") (pintype "passive"))
      (node (ref "X1") (pin "M3") (pinfunction "S3_M3") (pintype "passive"))
      (node (ref "X1") (pin "M4") (pinfunction "S4_M4") (pintype "passive"))
      (node (ref "X8") (pin "1-4") (pinfunction "4_1-4") (pintype "passive"))
      (node (ref "X8") (pin "2-4") (pinfunction "4_2-4") (pintype "passive"))
      (node (ref "X8") (pin "M1") (pinfunction "S1_M1") (pintype "passive"))
      (node (ref "X8") (pin "M2") (pinfunction "S2_M2") (pintype "passive"))
      (node (ref "X8") (pin "M3") (pinfunction "S3_M3") (pintype "passive"))
      (node (ref "X8") (pin "M4") (pinfunction "S4_M4") (pintype "passive"))
      (node (ref "Y1") (pin "2") (pinfunction "3_2") (pintype "passive"))
      (node (ref "Y1") (pin "4") (pinfunction "3_4") (pintype "passive"))
    )
    (net (code "19") (name "Net-(J2-CC1)") (class "Default")
      (node (ref "J2") (pin "A5") (pinfunction "CC1_A5") (pintype "bidirectional"))
      (node (ref "R9") (pin "1") (pinfunction "1_1") (pintype "passive"))
    )
    (net (code "20") (name "Net-(J2-CC2)") (class "Default")
      (node (ref "J2") (pin "B5") (pinfunction "CC2_B5") (pintype "bidirectional"))
      (node (ref "R1") (pin "1") (pinfunction "1_1") (pintype "passive"))
    )
    (net (code "21") (name "Net-(LED1-PadC)") (class "Default")
      (node (ref "LED1") (pin "C") (pinfunction "C_C") (pintype "passive"))
      (node (ref "R4") (pin "2") (pinfunction "2_2") (pintype "passive"))
    )
    (net (code "22") (name "Net-(LED2-PadC)") (class "Default")
      (node (ref "LED2") (pin "C") (pinfunction "C_C") (pintype "passive"))
      (node (ref "R10") (pin "2") (pinfunction "2_2") (pintype "passive"))
    )
    (net (code "23") (name "Net-(LED3-PadC)") (class "Default")
      (node (ref "LED3") (pin "C") (pinfunction "C_C") (pintype "passive"))
      (node (ref "R3") (pin "2") (pinfunction "2_2") (pintype "passive"))
    )
    (net (code "24") (name "Net-(SD1-CD{slash}DAT3(~{CS}))") (class "Default")
      (node (ref "SD1") (pin "2") (pinfunction "CD/DAT3(~{CS})_2") (pintype "bidirectional"))
      (node (ref "U$1") (pin "P$54") (pinfunction "PF4_P$54") (pintype "bidirectional"))
    )
    (net (code "25") (name "Net-(SD1-CLK(SCLK))") (class "Default")
      (node (ref "SD1") (pin "5") (pinfunction "CLK(SCLK)_5") (pintype "input"))
      (node (ref "U$1") (pin "P$56") (pinfunction "PF2_P$56") (pintype "bidirectional"))
    )
    (net (code "26") (name "Net-(SD1-CMD(DI))") (class "Default")
      (node (ref "SD1") (pin "3") (pinfunction "CMD(DI)_3") (pintype "bidirectional"))
      (node (ref "U$1") (pin "P$55") (pinfunction "PF3_P$55") (pintype "bidirectional"))
    )
    (net (code "27") (name "Net-(SD1-DAT0(DO))") (class "Default")
      (node (ref "SD1") (pin "7") (pinfunction "DAT0(DO)_7") (pintype "bidirectional"))
      (node (ref "U$1") (pin "P$57") (pinfunction "PF1_P$57") (pintype "bidirectional"))
    )
    (net (code "28") (name "Net-(SD1-DAT1)") (class "Default")
      (node (ref "SD1") (pin "8") (pinfunction "DAT1_8") (pintype "bidirectional"))
      (node (ref "U$1") (pin "P$58") (pinfunction "PF0_P$58") (pintype "bidirectional"))
    )
    (net (code "29") (name "Net-(SD1-DAT2)") (class "Default")
      (node (ref "SD1") (pin "1") (pinfunction "DAT2_1") (pintype "bidirectional"))
      (node (ref "U$1") (pin "P$53") (pinfunction "PF5_P$53") (pintype "bidirectional"))
    )
    (net (code "30") (name "Net-(SW20-2)") (class "Default")
      (node (ref "JP1") (pin "13") (pinfunction "13_13") (pintype "passive"))
      (node (ref "R2") (pin "2") (pinfunction "2_2") (pintype "passive"))
      (node (ref "SW20") (pin "P$2") (pinfunction "2_P$2") (pintype "bidirectional"))
      (node (ref "SW20") (pin "P$3") (pinfunction "3_P$3") (pintype "bidirectional"))
      (node (ref "U$1") (pin "P$70") (pinfunction "RESET_P$70") (pintype "bidirectional"))
      (node (ref "U1") (pin "26") (pinfunction "~{RESET}_26") (pintype "bidirectional"))
    )
    (net (code "31") (name "Net-(U$1-HOSCI)") (class "Default")
      (node (ref "C8") (pin "1") (pinfunction "1_1") (pintype "passive"))
      (node (ref "U$1") (pin "P$51") (pinfunction "HOSCI_P$51") (pintype "bidirectional"))
      (node (ref "Y1") (pin "1") (pinfunction "1_1") (pintype "passive"))
    )
    (net (code "32") (name "Net-(U$1-HOSCO)") (class "Default")
      (node (ref "C9") (pin "1") (pinfunction "1_1") (pintype "passive"))
      (node (ref "U$1") (pin "P$52") (pinfunction "HOSCO_P$52") (pintype "bidirectional"))
      (node (ref "Y1") (pin "3") (pinfunction "2_3") (pintype "passive"))
    )
    (net (code "33") (name "Net-(U$1-PD15)") (class "Default")
      (node (ref "JP1") (pin "40") (pinfunction "40_40") (pintype "passive"))
      (node (ref "U$1") (pin "P$23") (pinfunction "PD15_P$23") (pintype "bidirectional"))
    )
    (net (code "34") (name "Net-(U$1-PD16)") (class "Default")
      (node (ref "JP1") (pin "37") (pinfunction "37_37") (pintype "passive"))
      (node (ref "U$1") (pin "P$24") (pinfunction "PD16_P$24") (pintype "bidirectional"))
    )
    (net (code "35") (name "Net-(U$1-PD17)") (class "Default")
      (node (ref "JP2") (pin "1") (pinfunction "1_1") (pintype "passive"))
      (node (ref "U$1") (pin "P$25") (pinfunction "PD17_P$25") (pintype "bidirectional"))
      (node (ref "U2") (pin "10") (pinfunction "DC_10") (pintype "input"))
    )
    (net (code "36") (name "Net-(U$1-PD20)") (class "Default")
      (node (ref "JP2") (pin "2") (pinfunction "2_2") (pintype "passive"))
      (node (ref "R8") (pin "1") (pinfunction "1_1") (pintype "passive"))
      (node (ref "U$1") (pin "P$28") (pinfunction "PD20_P$28") (pintype "bidirectional"))
      (node (ref "U2") (pin "9") (pinfunction "/RES_9") (pintype "input"))
    )
    (net (code "37") (name "Net-(U$1-PD21)") (class "Default")
      (node (ref "JP2") (pin "3") (pinfunction "3_3") (pintype "passive"))
      (node (ref "U$1") (pin "P$29") (pinfunction "PD21_P$29") (pintype "bidirectional"))
      (node (ref "U2") (pin "8") (pinfunction "/CS_8") (pintype "input"))
    )
    (net (code "38") (name "Net-(U$1-PE2)") (class "Default")
      (node (ref "JP1") (pin "26") (pinfunction "26_26") (pintype "passive"))
      (node (ref "U$1") (pin "P$47") (pinfunction "PE2_P$47") (pintype "bidirectional"))
    )
    (net (code "39") (name "Net-(U$1-PE4)") (class "Default")
      (node (ref "JP1") (pin "27") (pinfunction "27_27") (pintype "passive"))
      (node (ref "U$1") (pin "P$45") (pinfunction "PE4_P$45") (pintype "bidirectional"))
    )
    (net (code "40") (name "Net-(U$1-PE5)") (class "Default")
      (node (ref "JP1") (pin "29") (pinfunction "29_29") (pintype "passive"))
      (node (ref "U$1") (pin "P$44") (pinfunction "PE5_P$44") (pintype "bidirectional"))
    )
    (net (code "41") (name "Net-(U$1-PE6)") (class "Default")
      (node (ref "JP1") (pin "32") (pinfunction "32_32") (pintype "passive"))
      (node (ref "U$1") (pin "P$43") (pinfunction "PE6_P$43") (pintype "bidirectional"))
    )
    (net (code "42") (name "Net-(U$1-PE7)") (class "Default")
      (node (ref "JP1") (pin "31") (pinfunction "31_31") (pintype "passive"))
      (node (ref "U$1") (pin "P$42") (pinfunction "PE7_P$42") (pintype "bidirectional"))
    )
    (net (code "43") (name "Net-(U$1-PE8)") (class "Default")
      (node (ref "JP1") (pin "33") (pinfunction "33_33") (pintype "passive"))
      (node (ref "U$1") (pin "P$41") (pinfunction "PE8_P$41") (pintype "bidirectional"))
    )
    (net (code "44") (name "Net-(U$1-PE9)") (class "Default")
      (node (ref "JP1") (pin "36") (pinfunction "36_36") (pintype "passive"))
      (node (ref "U$1") (pin "P$40") (pinfunction "PE9_P$40") (pintype "bidirectional"))
    )
    (net (code "45") (name "Net-(U$1-PE10)") (class "Default")
      (node (ref "JP1") (pin "35") (pinfunction "35_35") (pintype "passive"))
      (node (ref "U$1") (pin "P$39") (pinfunction "PE10_P$39") (pintype "bidirectional"))
    )
    (net (code "46") (name "Net-(U$1-SVREF)") (class "Default")
      (node (ref "R5") (pin "2") (pinfunction "2_2") (pintype "passive"))
      (node (ref "R6") (pin "1") (pinfunction "1_1") (pintype "passive"))
      (node (ref "U$1") (pin "P$33") (pinfunction "SVREF_P$33") (pintype "bidirectional"))
    )
    (net (code "47") (name "Net-(U$1-TPX1)") (class "Default")
      (node (ref "JP1") (pin "16") (pinfunction "16_16") (pintype "passive"))
      (node (ref "U$1") (pin "P$66") (pinfunction "TPX1_P$66") (pintype "bidirectional"))
    )
    (net (code "48") (name "Net-(U$1-TPX2)") (class "Default")
      (node (ref "JP1") (pin "15") (pinfunction "15_15") (pintype "passive"))
      (node (ref "U$1") (pin "P$65") (pinfunction "TPX2_P$65") (pintype "bidirectional"))
    )
    (net (code "49") (name "Net-(U$1-TPY1)") (class "Default")
      (node (ref "JP1") (pin "18") (pinfunction "18_18") (pintype "passive"))
      (node (ref "U$1") (pin "P$64") (pinfunction "TPY1_P$64") (pintype "bidirectional"))
    )
    (net (code "50") (name "Net-(U$1-TPY2)") (class "Default")
      (node (ref "JP1") (pin "22") (pinfunction "22_22") (pintype "passive"))
      (node (ref "U$1") (pin "P$63") (pinfunction "TPY2_P$63") (pintype "bidirectional"))
    )
    (net (code "51") (name "Net-(U$16-1)") (class "Default")
      (node (ref "C26") (pin "1") (pinfunction "1_1") (pintype "passive"))
      (node (ref "U$16") (pin "3") (pinfunction "1_3") (pintype "passive"))
      (node (ref "U1") (pin "32") (pinfunction "XTALOUT_32") (pintype "bidirectional"))
    )
    (net (code "52") (name "Net-(U$16-2)") (class "Default")
      (node (ref "C28") (pin "1") (pinfunction "1_1") (pintype "passive"))
      (node (ref "U$16") (pin "1") (pinfunction "2_1") (pintype "passive"))
      (node (ref "U1") (pin "33") (pinfunction "XTALIN/CLKIN_33") (pintype "bidirectional"))
    )
    (net (code "53") (name "Net-(U1A-D+)") (class "Default")
      (node (ref "U1") (pin "2") (pinfunction "D+_2") (pintype "bidirectional"))
      (node (ref "X1") (pin "1-3") (pinfunction "3_1-3") (pintype "passive"))
    )
    (net (code "54") (name "Net-(U1A-D-)") (class "Default")
      (node (ref "U1") (pin "1") (pinfunction "D-_1") (pintype "bidirectional"))
      (node (ref "X1") (pin "1-2") (pinfunction "2_1-2") (pintype "passive"))
    )
    (net (code "55") (name "Net-(U1B-D+)") (class "Default")
      (node (ref "U1") (pin "4") (pinfunction "D+_4") (pintype "bidirectional"))
      (node (ref "X1") (pin "2-3") (pinfunction "3_2-3") (pintype "passive"))
    )
    (net (code "56") (name "Net-(U1B-D-)") (class "Default")
      (node (ref "U1") (pin "3") (pinfunction "D-_3") (pintype "bidirectional"))
      (node (ref "X1") (pin "2-2") (pinfunction "2_2-2") (pintype "passive"))
    )
    (net (code "57") (name "Net-(U1C-D+)") (class "Default")
      (node (ref "U1") (pin "7") (pinfunction "D+_7") (pintype "bidirectional"))
      (node (ref "X8") (pin "1-3") (pinfunction "3_1-3") (pintype "passive"))
    )
    (net (code "58") (name "Net-(U1C-D-)") (class "Default")
      (node (ref "U1") (pin "6") (pinfunction "D-_6") (pintype "bidirectional"))
      (node (ref "X8") (pin "1-2") (pinfunction "2_1-2") (pintype "passive"))
    )
    (net (code "59") (name "Net-(U1D-D+)") (class "Default")
      (node (ref "U1") (pin "9") (pinfunction "D+_9") (pintype "bidirectional"))
      (node (ref "X8") (pin "2-3") (pinfunction "3_2-3") (pintype "passive"))
    )
    (net (code "60") (name "Net-(U1D-D-)") (class "Default")
      (node (ref "U1") (pin "8") (pinfunction "D-_8") (pintype "bidirectional"))
      (node (ref "X8") (pin "2-2") (pinfunction "2_2-2") (pintype "passive"))
    )
    (net (code "61") (name "Net-(U1E-CRFILT)") (class "Default")
      (node (ref "C31") (pin "1") (pinfunction "1_1") (pintype "passive"))
      (node (ref "U1") (pin "14") (pinfunction "CRFILT_14") (pintype "bidirectional"))
    )
    (net (code "62") (name "Net-(U1E-D+)") (class "Default")
      (node (ref "JP4") (pin "2") (pinfunction "2_2") (pintype "passive"))
      (node (ref "U1") (pin "31") (pinfunction "D+_31") (pintype "bidirectional"))
    )
    (net (code "63") (name "Net-(U1E-D-)") (class "Default")
      (node (ref "JP4") (pin "4") (pinfunction "4_4") (pintype "passive"))
      (node (ref "U1") (pin "30") (pinfunction "D-_30") (pintype "bidirectional"))
    )
    (net (code "64") (name "Net-(U1E-HS_IND{slash}CFG_SEL1)") (class "Default")
      (node (ref "R25") (pin "1") (pinfunction "1_1") (pintype "passive"))
      (node (ref "U1") (pin "25") (pinfunction "HS_IND/CFG_SEL1_25") (pintype "bidirectional"))
    )
    (net (code "65") (name "Net-(U1E-PLLFILT)") (class "Default")
      (node (ref "C30") (pin "1") (pinfunction "1_1") (pintype "passive"))
      (node (ref "U1") (pin "34") (pinfunction "PLLFILT_34") (pintype "bidirectional"))
    )
    (net (code "66") (name "Net-(U1E-RBIAS)") (class "Default")
      (node (ref "R20") (pin "2") (pinfunction "2_2") (pintype "passive"))
      (node (ref "U1") (pin "35") (pinfunction "RBIAS_35") (pintype "bidirectional"))
    )
    (net (code "67") (name "Net-(U1E-SCL{slash}SMBCLK{slash}CFG_SEL0)") (class "Default")
      (node (ref "R22") (pin "1") (pinfunction "1_1") (pintype "passive"))
      (node (ref "U1") (pin "24") (pinfunction "SCL/SMBCLK/CFG_SEL0_24") (pintype "bidirectional"))
    )
    (net (code "68") (name "Net-(U1E-SDA{slash}SMBDATA{slash}NON_REM1)") (class "Default")
      (node (ref "R23") (pin "1") (pinfunction "1_1") (pintype "passive"))
      (node (ref "U1") (pin "22") (pinfunction "SDA/SMBDATA/NON_REM1_22") (pintype "bidirectional"))
    )
    (net (code "69") (name "Net-(U1E-SUSP_IND{slash}LOCAL_PWR{slash}NON_REM0)") (class "Default")
      (node (ref "R16") (pin "1") (pinfunction "1_1") (pintype "passive"))
      (node (ref "U1") (pin "28") (pinfunction "SUSP_IND/LOCAL_PWR/NON_REM0_28") (pintype "bidirectional"))
    )
    (net (code "70") (name "Net-(U2-C1N)") (class "Default")
      (node (ref "C21") (pin "1") (pinfunction "1_1") (pintype "passive"))
      (node (ref "U2") (pin "4") (pinfunction "C1N_4") (pintype "input"))
    )
    (net (code "71") (name "Net-(U2-C1P)") (class "Default")
      (node (ref "C21") (pin "2") (pinfunction "2_2") (pintype "passive"))
      (node (ref "U2") (pin "3") (pinfunction "C1P_3") (pintype "input"))
    )
    (net (code "72") (name "Net-(U2-C2N)") (class "Default")
      (node (ref "C20") (pin "1") (pinfunction "1_1") (pintype "passive"))
      (node (ref "U2") (pin "2") (pinfunction "C2N_2") (pintype "input"))
    )
    (net (code "73") (name "Net-(U2-C2P)") (class "Default")
      (node (ref "C20") (pin "2") (pinfunction "2_2") (pintype "passive"))
      (node (ref "U2") (pin "1") (pinfunction "C2P_1") (pintype "input"))
    )
    (net (code "74") (name "Net-(U2-IREF)") (class "Default")
      (node (ref "R7") (pin "2") (pinfunction "2_2") (pintype "passive"))
      (node (ref "U2") (pin "13") (pinfunction "IREF_13") (pintype "input"))
    )
    (net (code "75") (name "Net-(U2-VCC)") (class "Default")
      (node (ref "C23") (pin "2") (pinfunction "2_2") (pintype "passive"))
      (node (ref "U2") (pin "15") (pinfunction "VCC_15") (pintype "power_in"))
    )
    (net (code "76") (name "Net-(U2-VCOMH)") (class "Default")
      (node (ref "C22") (pin "2") (pinfunction "2_2") (pintype "passive"))
      (node (ref "U2") (pin "14") (pinfunction "VCOMH_14") (pintype "output"))
    )
    (net (code "77") (name "Net-(U5-UD+)") (class "Default")
      (node (ref "J2") (pin "A6") (pinfunction "D+_A6") (pintype "bidirectional"))
      (node (ref "J2") (pin "B6") (pinfunction "D+_B6") (pintype "bidirectional"))
      (node (ref "U5") (pin "5") (pinfunction "UD+_5") (pintype "bidirectional"))
    )
    (net (code "78") (name "Net-(U5-UD-)") (class "Default")
      (node (ref "J2") (pin "A7") (pinfunction "D-_A7") (pintype "bidirectional"))
      (node (ref "J2") (pin "B7") (pinfunction "D-_B7") (pintype "bidirectional"))
      (node (ref "U5") (pin "6") (pinfunction "UD-_6") (pintype "bidirectional"))
    )
    (net (code "79") (name "unconnected-(JP1-Pad7)") (class "Default")
      (node (ref "JP1") (pin "7") (pinfunction "7_7") (pintype "passive"))
    )
    (net (code "80") (name "unconnected-(JP1-Pad11)") (class "Default")
      (node (ref "JP1") (pin "11") (pinfunction "11_11") (pintype "passive"))
    )
    (net (code "81") (name "unconnected-(JP1-Pad12)") (class "Default")
      (node (ref "JP1") (pin "12") (pinfunction "12_12") (pintype "passive"))
    )
    (net (code "82") (name "unconnected-(JP1-Pad38)") (class "Default")
      (node (ref "JP1") (pin "38") (pinfunction "38_38") (pintype "passive"))
    )
    (net (code "83") (name "unconnected-(SD1-~{CARD}-Pad9)") (class "Default")
      (node (ref "SD1") (pin "9") (pinfunction "~{CARD}_9") (pintype "passive"))
    )
    (net (code "84") (name "unconnected-(U$1-FMINL-PadP$84)") (class "Default")
      (node (ref "U$1") (pin "P$84") (pinfunction "FMINL_P$84") (pintype "bidirectional"))
    )
    (net (code "85") (name "unconnected-(U$1-FMINR-PadP$85)") (class "Default")
      (node (ref "U$1") (pin "P$85") (pinfunction "FMINR_P$85") (pintype "bidirectional"))
    )
    (net (code "86") (name "unconnected-(U$1-HPCOM-PadP$3)") (class "Default")
      (node (ref "U$1") (pin "P$3") (pinfunction "HPCOM_P$3") (pintype "bidirectional"))
    )
    (net (code "87") (name "unconnected-(U$1-HPCOMFB-PadP$2)") (class "Default")
      (node (ref "U$1") (pin "P$2") (pinfunction "HPCOMFB_P$2") (pintype "bidirectional"))
    )
    (net (code "88") (name "unconnected-(U$1-HPL-PadP$1)") (class "Default")
      (node (ref "U$1") (pin "P$1") (pinfunction "HPL_P$1") (pintype "bidirectional"))
    )
    (net (code "89") (name "unconnected-(U$1-HPR-PadP$88)") (class "Default")
      (node (ref "U$1") (pin "P$88") (pinfunction "HPR_P$88") (pintype "bidirectional"))
    )
    (net (code "90") (name "unconnected-(U$1-HPVCC-PadP$4)") (class "Default")
      (node (ref "U$1") (pin "P$4") (pinfunction "HPVCC_P$4") (pintype "bidirectional"))
    )
    (net (code "91") (name "unconnected-(U$1-LINL-PadP$86)") (class "Default")
      (node (ref "U$1") (pin "P$86") (pinfunction "LINL_P$86") (pintype "bidirectional"))
    )
    (net (code "92") (name "unconnected-(U$1-LRADC0-PadP$79)") (class "Default")
      (node (ref "U$1") (pin "P$79") (pinfunction "LRADC0_P$79") (pintype "bidirectional"))
    )
    (net (code "93") (name "unconnected-(U$1-MICIN-PadP$87)") (class "Default")
      (node (ref "U$1") (pin "P$87") (pinfunction "MICIN_P$87") (pintype "bidirectional"))
    )
    (net (code "94") (name "unconnected-(U$1-PD0-PadP$6)") (class "Default")
      (node (ref "U$1") (pin "P$6") (pinfunction "PD0_P$6") (pintype "bidirectional"))
    )
    (net (code "95") (name "unconnected-(U$1-PD1-PadP$7)") (class "Default")
      (node (ref "U$1") (pin "P$7") (pinfunction "PD1_P$7") (pintype "bidirectional"))
    )
    (net (code "96") (name "unconnected-(U$1-PD2-PadP$8)") (class "Default")
      (node (ref "U$1") (pin "P$8") (pinfunction "PD2_P$8") (pintype "bidirectional"))
    )
    (net (code "97") (name "unconnected-(U$1-PD3-PadP$9)") (class "Default")
      (node (ref "U$1") (pin "P$9") (pinfunction "PD3_P$9") (pintype "bidirectional"))
    )
    (net (code "98") (name "unconnected-(U$1-PD4-PadP$10)") (class "Default")
      (node (ref "U$1") (pin "P$10") (pinfunction "PD4_P$10") (pintype "bidirectional"))
    )
    (net (code "99") (name "unconnected-(U$1-PD5-PadP$11)") (class "Default")
      (node (ref "U$1") (pin "P$11") (pinfunction "PD5_P$11") (pintype "bidirectional"))
    )
    (net (code "100") (name "unconnected-(U$1-PD6-PadP$12)") (class "Default")
      (node (ref "U$1") (pin "P$12") (pinfunction "PD6_P$12") (pintype "bidirectional"))
    )
    (net (code "101") (name "unconnected-(U$1-PD7-PadP$13)") (class "Default")
      (node (ref "U$1") (pin "P$13") (pinfunction "PD7_P$13") (pintype "bidirectional"))
    )
    (net (code "102") (name "unconnected-(U$1-PD8-PadP$14)") (class "Default")
      (node (ref "U$1") (pin "P$14") (pinfunction "PD8_P$14") (pintype "bidirectional"))
    )
    (net (code "103") (name "unconnected-(U$1-PD9-PadP$15)") (class "Default")
      (node (ref "U$1") (pin "P$15") (pinfunction "PD9_P$15") (pintype "bidirectional"))
    )
    (net (code "104") (name "unconnected-(U$1-PD10-PadP$16)") (class "Default")
      (node (ref "U$1") (pin "P$16") (pinfunction "PD10_P$16") (pintype "bidirectional"))
    )
    (net (code "105") (name "unconnected-(U$1-PD11-PadP$17)") (class "Default")
      (node (ref "U$1") (pin "P$17") (pinfunction "PD11_P$17") (pintype "bidirectional"))
    )
    (net (code "106") (name "unconnected-(U$1-PD12-PadP$18)") (class "Default")
      (node (ref "U$1") (pin "P$18") (pinfunction "PD12_P$18") (pintype "bidirectional"))
    )
    (net (code "107") (name "unconnected-(U$1-PD18-PadP$26)") (class "Default")
      (node (ref "U$1") (pin "P$26") (pinfunction "PD18_P$26") (pintype "bidirectional"))
    )
    (net (code "108") (name "unconnected-(U$1-PD19-PadP$27)") (class "Default")
      (node (ref "U$1") (pin "P$27") (pinfunction "PD19_P$27") (pintype "bidirectional"))
    )
    (net (code "109") (name "unconnected-(U$1-TV-VRN-PadP$75)") (class "Default")
      (node (ref "U$1") (pin "P$75") (pinfunction "TV-VRN_P$75") (pintype "bidirectional"))
    )
    (net (code "110") (name "unconnected-(U$1-TV-VRP-PadP$76)") (class "Default")
      (node (ref "U$1") (pin "P$76") (pinfunction "TV-VRP_P$76") (pintype "bidirectional"))
    )
    (net (code "111") (name "unconnected-(U$1-TVIN0-PadP$78)") (class "Default")
      (node (ref "U$1") (pin "P$78") (pinfunction "TVIN0_P$78") (pintype "bidirectional"))
    )
    (net (code "112") (name "unconnected-(U$1-TVIN1-PadP$77)") (class "Default")
      (node (ref "U$1") (pin "P$77") (pinfunction "TVIN1_P$77") (pintype "bidirectional"))
    )
    (net (code "113") (name "unconnected-(U$1-TVOUT-PadP$72)") (class "Default")
      (node (ref "U$1") (pin "P$72") (pinfunction "TVOUT_P$72") (pintype "bidirectional"))
    )
    (net (code "114") (name "unconnected-(U$1-VRA1-PadP$81)") (class "Default")
      (node (ref "U$1") (pin "P$81") (pinfunction "VRA1_P$81") (pintype "bidirectional"))
    )
    (net (code "115") (name "unconnected-(U$1-VRA2-PadP$83)") (class "Default")
      (node (ref "U$1") (pin "P$83") (pinfunction "VRA2_P$83") (pintype "bidirectional"))
    )
    (net (code "116") (name "unconnected-(U1A-PRTPWR-Pad12)") (class "Default")
      (node (ref "U1") (pin "12") (pinfunction "PRTPWR_12") (pintype "bidirectional"))
    )
    (net (code "117") (name "unconnected-(U1A-~{OCS}-Pad13)") (class "Default")
      (node (ref "U1") (pin "13") (pinfunction "~{OCS}_13") (pintype "bidirectional"))
    )
    (net (code "118") (name "unconnected-(U1B-PRTPWR-Pad16)") (class "Default")
      (node (ref "U1") (pin "16") (pinfunction "PRTPWR_16") (pintype "bidirectional"))
    )
    (net (code "119") (name "unconnected-(U1B-~{OCS}-Pad17)") (class "Default")
      (node (ref "U1") (pin "17") (pinfunction "~{OCS}_17") (pintype "bidirectional"))
    )
    (net (code "120") (name "unconnected-(U1C-PRTPWR-Pad18)") (class "Default")
      (node (ref "U1") (pin "18") (pinfunction "PRTPWR_18") (pintype "bidirectional"))
    )
    (net (code "121") (name "unconnected-(U1C-~{OCS}-Pad19)") (class "Default")
      (node (ref "U1") (pin "19") (pinfunction "~{OCS}_19") (pintype "bidirectional"))
    )
    (net (code "122") (name "unconnected-(U1D-PRTPWR-Pad20)") (class "Default")
      (node (ref "U1") (pin "20") (pinfunction "PRTPWR_20") (pintype "bidirectional"))
    )
    (net (code "123") (name "unconnected-(U1D-~{OCS}-Pad21)") (class "Default")
      (node (ref "U1") (pin "21") (pinfunction "~{OCS}_21") (pintype "bidirectional"))
    )
    (net (code "124") (name "unconnected-(U1E-TEST-Pad11)") (class "Default")
      (node (ref "U1") (pin "11") (pinfunction "TEST_11") (pintype "bidirectional"))
    )
    (net (code "125") (name "unconnected-(U5-R232-Pad15)") (class "Default")
      (node (ref "U5") (pin "15") (pinfunction "R232_15") (pintype "bidirectional"))
    )
    (net (code "126") (name "unconnected-(U5-~{CTS}-Pad9)") (class "Default")
      (node (ref "U5") (pin "9") (pinfunction "~{CTS}_9") (pintype "bidirectional"))
    )
    (net (code "127") (name "unconnected-(U5-~{DCD}-Pad12)") (class "Default")
      (node (ref "U5") (pin "12") (pinfunction "~{DCD}_12") (pintype "bidirectional"))
    )
    (net (code "128") (name "unconnected-(U5-~{DSR}-Pad10)") (class "Default")
      (node (ref "U5") (pin "10") (pinfunction "~{DSR}_10") (pintype "bidirectional"))
    )
    (net (code "129") (name "unconnected-(U5-~{DTR}-Pad13)") (class "Default")
      (node (ref "U5") (pin "13") (pinfunction "~{DTR}_13") (pintype "bidirectional"))
    )
    (net (code "130") (name "unconnected-(U5-~{RI}-Pad11)") (class "Default")
      (node (ref "U5") (pin "11") (pinfunction "~{RI}_11") (pintype "bidirectional"))
    )
    (net (code "131") (name "unconnected-(U5-~{RTS}-Pad14)") (class "Default")
      (node (ref "U5") (pin "14") (pinfunction "~{RTS}_14") (pintype "bidirectional"))
    )
  )
)
